# IPH11VIBRATOR.net
KiCad netlist of a schematic drawn in Altium Designer
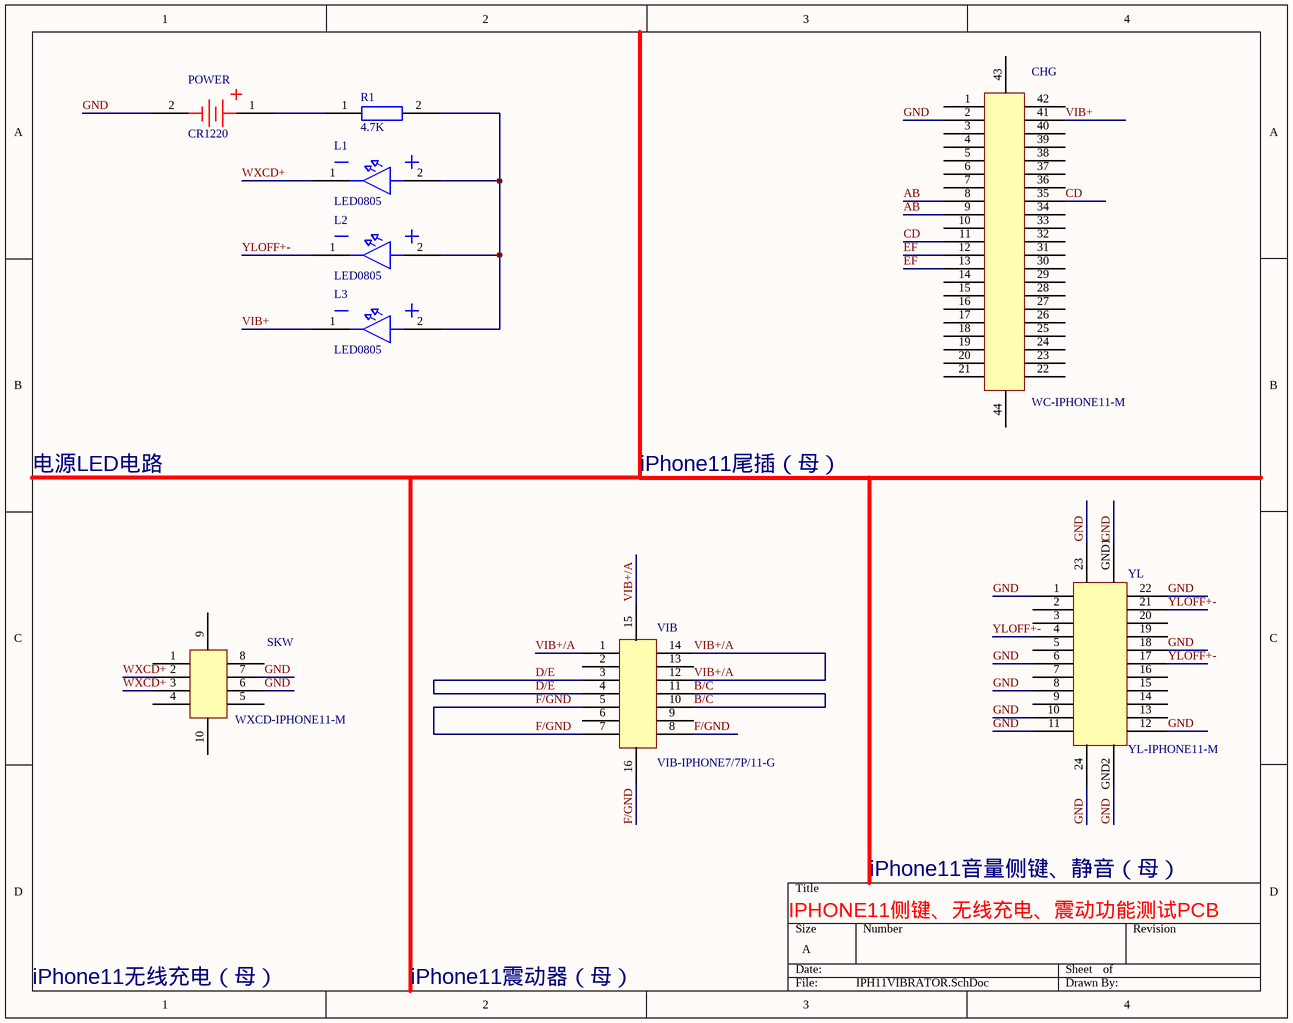
[diagram p0: IPH11VIBRATOR.SchDoc]

(export (version "E")
  (design (tool "Eeschema 10.0.6"))
  (components
    (comp (ref "CHG")
      (value "WC-IPHONE11-M")
      (footprint "IPHONE11-WC-M")
      (libsource (lib "iPhone") (part "WC-IPHONE11-M"))
    )
    (comp (ref "L1") (value "LED0805") (footprint "LED0805") (libsource (lib "iPhone") (part "LED0805")))
    (comp (ref "L2") (value "LED0805") (footprint "LED0805") (libsource (lib "iPhone") (part "LED0805")))
    (comp (ref "L3") (value "LED0805") (footprint "LED0805") (libsource (lib "iPhone") (part "LED0805")))
    (comp (ref "POWER") (value "CR1220") (footprint "CR1220") (libsource (lib "iPhone") (part "CR2016")))
    (comp (ref "R1") (value "4.7K") (footprint "R0805") (libsource (lib "iPhone") (part "R0805")))
    (comp (ref "SKW")
      (value "WXCD-IPHONE11-M")
      (footprint "IPHONE11-WXCD-M")
      (libsource (lib "iPhone") (part "WXCD-IPHONE11-M"))
    )
    (comp (ref "VIB")
      (value "VIB-IPHONE7/7P/11-G")
      (footprint "IPHONE7/7P/11-VIB-G")
      (libsource (lib "iPhone") (part "VIB-IPHONE7/7P/11-G"))
    )
    (comp (ref "YL")
      (value "YL-IPHONE11-M")
      (footprint "IPHONE11-YL-M")
      (libsource (lib "iPhone") (part "YL-IPHONE11-M"))
    )
  )
  (nets
    (net (code "1") (name "/AB") (class "Default")
      (node (ref "CHG") (pin "8") (pintype "passive"))
      (node (ref "CHG") (pin "9") (pintype "passive"))
    )
    (net (code "2") (name "/B{slash}C") (class "Default")
      (node (ref "VIB") (pin "10") (pintype "passive"))
      (node (ref "VIB") (pin "11") (pintype "passive"))
    )
    (net (code "3") (name "/CD") (class "Default")
      (node (ref "CHG") (pin "11") (pintype "passive"))
      (node (ref "CHG") (pin "35") (pintype "passive"))
    )
    (net (code "4") (name "/D{slash}E") (class "Default")
      (node (ref "VIB") (pin "3") (pintype "passive"))
      (node (ref "VIB") (pin "4") (pintype "passive"))
    )
    (net (code "5") (name "/EF") (class "Default")
      (node (ref "CHG") (pin "12") (pintype "passive"))
      (node (ref "CHG") (pin "13") (pintype "passive"))
    )
    (net (code "6") (name "/F{slash}GND") (class "Default")
      (node (ref "VIB") (pin "16") (pintype "passive"))
      (node (ref "VIB") (pin "5") (pintype "passive"))
      (node (ref "VIB") (pin "7") (pintype "passive"))
      (node (ref "VIB") (pin "8") (pintype "passive"))
    )
    (net (code "7") (name "/GND") (class "Default")
      (node (ref "CHG") (pin "2") (pintype "passive"))
      (node (ref "POWER") (pin "2") (pintype "passive"))
      (node (ref "SKW") (pin "6") (pintype "passive"))
      (node (ref "SKW") (pin "7") (pintype "passive"))
      (node (ref "YL") (pin "1") (pintype "passive"))
      (node (ref "YL") (pin "10") (pintype "passive"))
      (node (ref "YL") (pin "11") (pintype "passive"))
      (node (ref "YL") (pin "12") (pintype "passive"))
      (node (ref "YL") (pin "18") (pintype "passive"))
      (node (ref "YL") (pin "22") (pintype "passive"))
      (node (ref "YL") (pin "23") (pintype "passive"))
      (node (ref "YL") (pin "24") (pintype "passive"))
      (node (ref "YL") (pin "6") (pintype "passive"))
      (node (ref "YL") (pin "8") (pintype "passive"))
      (node (ref "YL") (pin "GND1") (pintype "passive"))
      (node (ref "YL") (pin "GND2") (pintype "passive"))
    )
    (net (code "8") (name "/VIB+") (class "Default")
      (node (ref "CHG") (pin "41") (pintype "passive"))
      (node (ref "L3") (pin "1") (pintype "passive"))
    )
    (net (code "9") (name "/VIB+{slash}A") (class "Default")
      (node (ref "VIB") (pin "1") (pintype "passive"))
      (node (ref "VIB") (pin "12") (pintype "passive"))
      (node (ref "VIB") (pin "14") (pintype "passive"))
      (node (ref "VIB") (pin "15") (pintype "passive"))
    )
    (net (code "10") (name "/WXCD+") (class "Default")
      (node (ref "L1") (pin "1") (pintype "passive"))
      (node (ref "SKW") (pin "2") (pintype "passive"))
      (node (ref "SKW") (pin "3") (pintype "passive"))
    )
    (net (code "11") (name "/YLOFF+-") (class "Default")
      (node (ref "L2") (pin "1") (pintype "passive"))
      (node (ref "YL") (pin "17") (pintype "passive"))
      (node (ref "YL") (pin "21") (pintype "passive"))
      (node (ref "YL") (pin "4") (pintype "passive"))
    )
    (net (code "12") (name "Net-(L1-Pad2)") (class "Default")
      (node (ref "L1") (pin "2") (pintype "passive"))
      (node (ref "L2") (pin "2") (pintype "passive"))
      (node (ref "L3") (pin "2") (pintype "passive"))
      (node (ref "R1") (pin "2") (pintype "passive"))
    )
    (net (code "13") (name "Net-(POWER-Pad1)") (class "Default")
      (node (ref "POWER") (pin "1") (pintype "passive"))
      (node (ref "R1") (pin "1") (pintype "passive"))
    )
    (net (code "14") (name "unconnected-(CHG-Pad1)") (class "Default")
      (node (ref "CHG") (pin "1") (pintype "passive"))
    )
    (net (code "15") (name "unconnected-(CHG-Pad3)") (class "Default")
      (node (ref "CHG") (pin "3") (pintype "passive"))
    )
    (net (code "16") (name "unconnected-(CHG-Pad4)") (class "Default")
      (node (ref "CHG") (pin "4") (pintype "passive"))
    )
    (net (code "17") (name "unconnected-(CHG-Pad5)") (class "Default")
      (node (ref "CHG") (pin "5") (pintype "passive"))
    )
    (net (code "18") (name "unconnected-(CHG-Pad6)") (class "Default")
      (node (ref "CHG") (pin "6") (pintype "passive"))
    )
    (net (code "19") (name "unconnected-(CHG-Pad7)") (class "Default")
      (node (ref "CHG") (pin "7") (pintype "passive"))
    )
    (net (code "20") (name "unconnected-(CHG-Pad10)") (class "Default")
      (node (ref "CHG") (pin "10") (pintype "passive"))
    )
    (net (code "21") (name "unconnected-(CHG-Pad14)") (class "Default")
      (node (ref "CHG") (pin "14") (pintype "passive"))
    )
    (net (code "22") (name "unconnected-(CHG-Pad15)") (class "Default")
      (node (ref "CHG") (pin "15") (pintype "passive"))
    )
    (net (code "23") (name "unconnected-(CHG-Pad16)") (class "Default")
      (node (ref "CHG") (pin "16") (pintype "passive"))
    )
    (net (code "24") (name "unconnected-(CHG-Pad17)") (class "Default")
      (node (ref "CHG") (pin "17") (pintype "passive"))
    )
    (net (code "25") (name "unconnected-(CHG-Pad18)") (class "Default")
      (node (ref "CHG") (pin "18") (pintype "passive"))
    )
    (net (code "26") (name "unconnected-(CHG-Pad19)") (class "Default")
      (node (ref "CHG") (pin "19") (pintype "passive"))
    )
    (net (code "27") (name "unconnected-(CHG-Pad20)") (class "Default")
      (node (ref "CHG") (pin "20") (pintype "passive"))
    )
    (net (code "28") (name "unconnected-(CHG-Pad21)") (class "Default")
      (node (ref "CHG") (pin "21") (pintype "passive"))
    )
    (net (code "29") (name "unconnected-(CHG-Pad22)") (class "Default")
      (node (ref "CHG") (pin "22") (pintype "passive"))
    )
    (net (code "30") (name "unconnected-(CHG-Pad23)") (class "Default")
      (node (ref "CHG") (pin "23") (pintype "passive"))
    )
    (net (code "31") (name "unconnected-(CHG-Pad24)") (class "Default")
      (node (ref "CHG") (pin "24") (pintype "passive"))
    )
    (net (code "32") (name "unconnected-(CHG-Pad25)") (class "Default")
      (node (ref "CHG") (pin "25") (pintype "passive"))
    )
    (net (code "33") (name "unconnected-(CHG-Pad26)") (class "Default")
      (node (ref "CHG") (pin "26") (pintype "passive"))
    )
    (net (code "34") (name "unconnected-(CHG-Pad27)") (class "Default")
      (node (ref "CHG") (pin "27") (pintype "passive"))
    )
    (net (code "35") (name "unconnected-(CHG-Pad28)") (class "Default")
      (node (ref "CHG") (pin "28") (pintype "passive"))
    )
    (net (code "36") (name "unconnected-(CHG-Pad29)") (class "Default")
      (node (ref "CHG") (pin "29") (pintype "passive"))
    )
    (net (code "37") (name "unconnected-(CHG-Pad30)") (class "Default")
      (node (ref "CHG") (pin "30") (pintype "passive"))
    )
    (net (code "38") (name "unconnected-(CHG-Pad31)") (class "Default")
      (node (ref "CHG") (pin "31") (pintype "passive"))
    )
    (net (code "39") (name "unconnected-(CHG-Pad32)") (class "Default")
      (node (ref "CHG") (pin "32") (pintype "passive"))
    )
    (net (code "40") (name "unconnected-(CHG-Pad33)") (class "Default")
      (node (ref "CHG") (pin "33") (pintype "passive"))
    )
    (net (code "41") (name "unconnected-(CHG-Pad34)") (class "Default")
      (node (ref "CHG") (pin "34") (pintype "passive"))
    )
    (net (code "42") (name "unconnected-(CHG-Pad36)") (class "Default")
      (node (ref "CHG") (pin "36") (pintype "passive"))
    )
    (net (code "43") (name "unconnected-(CHG-Pad37)") (class "Default")
      (node (ref "CHG") (pin "37") (pintype "passive"))
    )
    (net (code "44") (name "unconnected-(CHG-Pad38)") (class "Default")
      (node (ref "CHG") (pin "38") (pintype "passive"))
    )
    (net (code "45") (name "unconnected-(CHG-Pad39)") (class "Default")
      (node (ref "CHG") (pin "39") (pintype "passive"))
    )
    (net (code "46") (name "unconnected-(CHG-Pad40)") (class "Default")
      (node (ref "CHG") (pin "40") (pintype "passive"))
    )
    (net (code "47") (name "unconnected-(CHG-Pad42)") (class "Default")
      (node (ref "CHG") (pin "42") (pintype "passive"))
    )
    (net (code "48") (name "unconnected-(CHG-Pad43)") (class "Default")
      (node (ref "CHG") (pin "43") (pintype "passive"))
    )
    (net (code "49") (name "unconnected-(CHG-Pad44)") (class "Default")
      (node (ref "CHG") (pin "44") (pintype "passive"))
    )
    (net (code "50") (name "unconnected-(SKW-Pad1)") (class "Default")
      (node (ref "SKW") (pin "1") (pintype "passive"))
    )
    (net (code "51") (name "unconnected-(SKW-Pad4)") (class "Default")
      (node (ref "SKW") (pin "4") (pintype "passive"))
    )
    (net (code "52") (name "unconnected-(SKW-Pad5)") (class "Default")
      (node (ref "SKW") (pin "5") (pintype "passive"))
    )
    (net (code "53") (name "unconnected-(SKW-Pad8)") (class "Default")
      (node (ref "SKW") (pin "8") (pintype "passive"))
    )
    (net (code "54") (name "unconnected-(SKW-Pad9)") (class "Default")
      (node (ref "SKW") (pin "9") (pintype "passive"))
    )
    (net (code "55") (name "unconnected-(SKW-Pad10)") (class "Default")
      (node (ref "SKW") (pin "10") (pintype "passive"))
    )
    (net (code "56") (name "unconnected-(VIB-Pad2)") (class "Default")
      (node (ref "VIB") (pin "2") (pintype "passive"))
    )
    (net (code "57") (name "unconnected-(VIB-Pad6)") (class "Default")
      (node (ref "VIB") (pin "6") (pintype "passive"))
    )
    (net (code "58") (name "unconnected-(VIB-Pad9)") (class "Default")
      (node (ref "VIB") (pin "9") (pintype "passive"))
    )
    (net (code "59") (name "unconnected-(VIB-Pad13)") (class "Default")
      (node (ref "VIB") (pin "13") (pintype "passive"))
    )
    (net (code "60") (name "unconnected-(YL-Pad2)") (class "Default")
      (node (ref "YL") (pin "2") (pintype "passive"))
    )
    (net (code "61") (name "unconnected-(YL-Pad3)") (class "Default")
      (node (ref "YL") (pin "3") (pintype "passive"))
    )
    (net (code "62") (name "unconnected-(YL-Pad5)") (class "Default")
      (node (ref "YL") (pin "5") (pintype "passive"))
    )
    (net (code "63") (name "unconnected-(YL-Pad7)") (class "Default")
      (node (ref "YL") (pin "7") (pintype "passive"))
    )
    (net (code "64") (name "unconnected-(YL-Pad9)") (class "Default")
      (node (ref "YL") (pin "9") (pintype "passive"))
    )
    (net (code "65") (name "unconnected-(YL-Pad13)") (class "Default")
      (node (ref "YL") (pin "13") (pintype "passive"))
    )
    (net (code "66") (name "unconnected-(YL-Pad14)") (class "Default")
      (node (ref "YL") (pin "14") (pintype "passive"))
    )
    (net (code "67") (name "unconnected-(YL-Pad15)") (class "Default")
      (node (ref "YL") (pin "15") (pintype "passive"))
    )
    (net (code "68") (name "unconnected-(YL-Pad16)") (class "Default")
      (node (ref "YL") (pin "16") (pintype "passive"))
    )
    (net (code "69") (name "unconnected-(YL-Pad19)") (class "Default")
      (node (ref "YL") (pin "19") (pintype "passive"))
    )
    (net (code "70") (name "unconnected-(YL-Pad20)") (class "Default")
      (node (ref "YL") (pin "20") (pintype "passive"))
    )
  )
)
